# cherrymx_rgb_8row_breakout.net
KiCad netlist of a schematic drawn in EAGLE
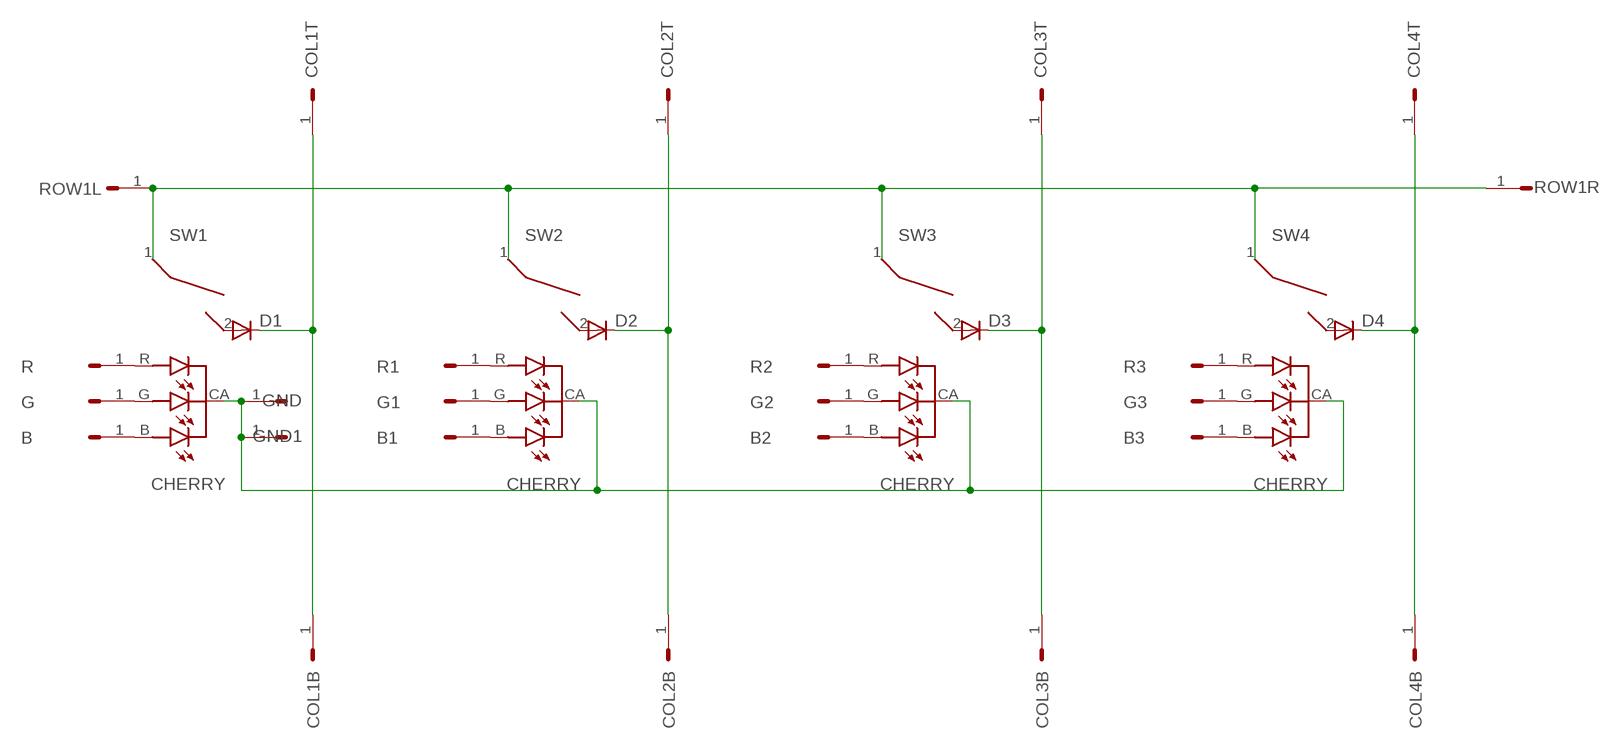
[diagram p0: schematic, sheet 1]

(export (version "E")
  (design (tool "Eeschema 10.0.6"))
  (components
    (comp (ref "B")
      (value "HEADER/MALE/01")
      (footprint "eagle-import:HEADER_MALE_01")
      (libsource (lib "eagle-import") (part "HEADER/MALE/01"))
    )
    (comp (ref "B1")
      (value "HEADER/MALE/01")
      (footprint "eagle-import:HEADER_MALE_01")
      (fields (field (name "SPICEPREFIX") "X"))
      (libsource (lib "eagle-import") (part "HEADER/MALE/01"))
    )
    (comp (ref "B2")
      (value "HEADER/MALE/01")
      (footprint "eagle-import:HEADER_MALE_01")
      (libsource (lib "eagle-import") (part "HEADER/MALE/01"))
    )
    (comp (ref "B3")
      (value "HEADER/MALE/01")
      (footprint "eagle-import:HEADER_MALE_01")
      (libsource (lib "eagle-import") (part "HEADER/MALE/01"))
    )
    (comp (ref "COL1B")
      (value "HEADER/MALE/01")
      (footprint "eagle-import:HEADER_MALE_01")
      (libsource (lib "eagle-import") (part "HEADER/MALE/01"))
    )
    (comp (ref "COL1T")
      (value "HEADER/MALE/01")
      (footprint "eagle-import:HEADER_MALE_01")
      (libsource (lib "eagle-import") (part "HEADER/MALE/01"))
    )
    (comp (ref "COL2B")
      (value "HEADER/MALE/01")
      (footprint "eagle-import:HEADER_MALE_01")
      (fields (field (name "SPICEPREFIX") "X"))
      (libsource (lib "eagle-import") (part "HEADER/MALE/01"))
    )
    (comp (ref "COL2T")
      (value "HEADER/MALE/01")
      (footprint "eagle-import:HEADER_MALE_01")
      (fields (field (name "SPICEPREFIX") "X"))
      (libsource (lib "eagle-import") (part "HEADER/MALE/01"))
    )
    (comp (ref "COL3B")
      (value "HEADER/MALE/01")
      (footprint "eagle-import:HEADER_MALE_01")
      (libsource (lib "eagle-import") (part "HEADER/MALE/01"))
    )
    (comp (ref "COL3T")
      (value "HEADER/MALE/01")
      (footprint "eagle-import:HEADER_MALE_01")
      (libsource (lib "eagle-import") (part "HEADER/MALE/01"))
    )
    (comp (ref "COL4B")
      (value "HEADER/MALE/01")
      (footprint "eagle-import:HEADER_MALE_01")
      (libsource (lib "eagle-import") (part "HEADER/MALE/01"))
    )
    (comp (ref "COL4T")
      (value "HEADER/MALE/01")
      (footprint "eagle-import:HEADER_MALE_01")
      (libsource (lib "eagle-import") (part "HEADER/MALE/01"))
    )
    (comp (ref "D1")
      (value "1N4148DO35-7")
      (footprint "eagle-import:DO35-7")
      (libsource (lib "eagle-import") (part "1N4148DO35-7"))
    )
    (comp (ref "D2")
      (value "1N4148DO35-7")
      (footprint "eagle-import:DO35-7")
      (fields (field (name "SPICEPREFIX") "D"))
      (libsource (lib "eagle-import") (part "1N4148DO35-7"))
    )
    (comp (ref "D3")
      (value "1N4148DO35-7")
      (footprint "eagle-import:DO35-7")
      (libsource (lib "eagle-import") (part "1N4148DO35-7"))
    )
    (comp (ref "D4")
      (value "1N4148DO35-7")
      (footprint "eagle-import:DO35-7")
      (libsource (lib "eagle-import") (part "1N4148DO35-7"))
    )
    (comp (ref "G")
      (value "HEADER/MALE/01")
      (footprint "eagle-import:HEADER_MALE_01")
      (libsource (lib "eagle-import") (part "HEADER/MALE/01"))
    )
    (comp (ref "G1")
      (value "HEADER/MALE/01")
      (footprint "eagle-import:HEADER_MALE_01")
      (fields (field (name "SPICEPREFIX") "X"))
      (libsource (lib "eagle-import") (part "HEADER/MALE/01"))
    )
    (comp (ref "G2")
      (value "HEADER/MALE/01")
      (footprint "eagle-import:HEADER_MALE_01")
      (libsource (lib "eagle-import") (part "HEADER/MALE/01"))
    )
    (comp (ref "G3")
      (value "HEADER/MALE/01")
      (footprint "eagle-import:HEADER_MALE_01")
      (libsource (lib "eagle-import") (part "HEADER/MALE/01"))
    )
    (comp (ref "GND")
      (value "HEADER/MALE/01")
      (footprint "eagle-import:HEADER_MALE_01")
      (libsource (lib "eagle-import") (part "HEADER/MALE/01"))
    )
    (comp (ref "GND1")
      (value "HEADER/MALE/01")
      (footprint "eagle-import:HEADER_MALE_01")
      (libsource (lib "eagle-import") (part "HEADER/MALE/01"))
    )
    (comp (ref "R")
      (value "HEADER/MALE/01")
      (footprint "eagle-import:HEADER_MALE_01")
      (libsource (lib "eagle-import") (part "HEADER/MALE/01"))
    )
    (comp (ref "R1")
      (value "HEADER/MALE/01")
      (footprint "eagle-import:HEADER_MALE_01")
      (fields (field (name "SPICEPREFIX") "X"))
      (libsource (lib "eagle-import") (part "HEADER/MALE/01"))
    )
    (comp (ref "R2")
      (value "HEADER/MALE/01")
      (footprint "eagle-import:HEADER_MALE_01")
      (libsource (lib "eagle-import") (part "HEADER/MALE/01"))
    )
    (comp (ref "R3")
      (value "HEADER/MALE/01")
      (footprint "eagle-import:HEADER_MALE_01")
      (libsource (lib "eagle-import") (part "HEADER/MALE/01"))
    )
    (comp (ref "ROW1L")
      (value "HEADER/MALE/01")
      (footprint "eagle-import:HEADER_MALE_01")
      (libsource (lib "eagle-import") (part "HEADER/MALE/01"))
    )
    (comp (ref "ROW1R")
      (value "HEADER/MALE/01")
      (footprint "eagle-import:HEADER_MALE_01")
      (libsource (lib "eagle-import") (part "HEADER/MALE/01"))
    )
    (comp (ref "SW1")
      (value "CHERRY")
      (footprint "eagle-import:SWITCH_CHERRY_MX_RGB")
      (libsource (lib "eagle-import") (part "SWITCH_CHERRY_MX_RGBSWITCH_CHERRY_MX_RGB"))
    )
    (comp (ref "SW2")
      (value "CHERRY")
      (footprint "eagle-import:SWITCH_CHERRY_MX_RGB")
      (fields (field (name "SPICEPREFIX") "X"))
      (libsource (lib "eagle-import") (part "SWITCH_CHERRY_MX_RGBSWITCH_CHERRY_MX_RGB"))
    )
    (comp (ref "SW3")
      (value "CHERRY")
      (footprint "eagle-import:SWITCH_CHERRY_MX_RGB")
      (libsource (lib "eagle-import") (part "SWITCH_CHERRY_MX_RGBSWITCH_CHERRY_MX_RGB"))
    )
    (comp (ref "SW4")
      (value "CHERRY")
      (footprint "eagle-import:SWITCH_CHERRY_MX_RGB")
      (libsource (lib "eagle-import") (part "SWITCH_CHERRY_MX_RGBSWITCH_CHERRY_MX_RGB"))
    )
  )
  (nets
    (net (code "1") (name "Net-(B-3)") (class "Default")
      (node (ref "B") (pin "1") (pinfunction "3_1") (pintype "passive"))
      (node (ref "SW1") (pin "B") (pinfunction "B-CAT_B") (pintype "passive"))
    )
    (net (code "2") (name "Net-(B1-3)") (class "Default")
      (node (ref "B1") (pin "1") (pinfunction "3_1") (pintype "passive"))
      (node (ref "SW2") (pin "B") (pinfunction "B-CAT_B") (pintype "passive"))
    )
    (net (code "3") (name "Net-(B2-3)") (class "Default")
      (node (ref "B2") (pin "1") (pinfunction "3_1") (pintype "passive"))
      (node (ref "SW3") (pin "B") (pinfunction "B-CAT_B") (pintype "passive"))
    )
    (net (code "4") (name "Net-(B3-3)") (class "Default")
      (node (ref "B3") (pin "1") (pinfunction "3_1") (pintype "passive"))
      (node (ref "SW4") (pin "B") (pinfunction "B-CAT_B") (pintype "passive"))
    )
    (net (code "5") (name "Net-(COL1B-3)") (class "Default")
      (node (ref "COL1B") (pin "1") (pinfunction "3_1") (pintype "passive"))
      (node (ref "COL1T") (pin "1") (pinfunction "3_1") (pintype "passive"))
      (node (ref "D1") (pin "C") (pinfunction "C_C") (pintype "passive"))
    )
    (net (code "6") (name "Net-(COL2B-3)") (class "Default")
      (node (ref "COL2B") (pin "1") (pinfunction "3_1") (pintype "passive"))
      (node (ref "COL2T") (pin "1") (pinfunction "3_1") (pintype "passive"))
      (node (ref "D2") (pin "C") (pinfunction "C_C") (pintype "passive"))
    )
    (net (code "7") (name "Net-(COL3B-3)") (class "Default")
      (node (ref "COL3B") (pin "1") (pinfunction "3_1") (pintype "passive"))
      (node (ref "COL3T") (pin "1") (pinfunction "3_1") (pintype "passive"))
      (node (ref "D3") (pin "C") (pinfunction "C_C") (pintype "passive"))
    )
    (net (code "8") (name "Net-(COL4B-3)") (class "Default")
      (node (ref "COL4B") (pin "1") (pinfunction "3_1") (pintype "passive"))
      (node (ref "COL4T") (pin "1") (pinfunction "3_1") (pintype "passive"))
      (node (ref "D4") (pin "C") (pinfunction "C_C") (pintype "passive"))
    )
    (net (code "9") (name "Net-(D1-PadA)") (class "Default")
      (node (ref "D1") (pin "A") (pinfunction "A_A") (pintype "passive"))
      (node (ref "SW1") (pin "2") (pinfunction "2_2") (pintype "passive"))
    )
    (net (code "10") (name "Net-(D2-PadA)") (class "Default")
      (node (ref "D2") (pin "A") (pinfunction "A_A") (pintype "passive"))
      (node (ref "SW2") (pin "2") (pinfunction "2_2") (pintype "passive"))
    )
    (net (code "11") (name "Net-(D3-PadA)") (class "Default")
      (node (ref "D3") (pin "A") (pinfunction "A_A") (pintype "passive"))
      (node (ref "SW3") (pin "2") (pinfunction "2_2") (pintype "passive"))
    )
    (net (code "12") (name "Net-(D4-PadA)") (class "Default")
      (node (ref "D4") (pin "A") (pinfunction "A_A") (pintype "passive"))
      (node (ref "SW4") (pin "2") (pinfunction "2_2") (pintype "passive"))
    )
    (net (code "13") (name "Net-(G-3)") (class "Default")
      (node (ref "G") (pin "1") (pinfunction "3_1") (pintype "passive"))
      (node (ref "SW1") (pin "G") (pinfunction "G-CAT_G") (pintype "passive"))
    )
    (net (code "14") (name "Net-(G1-3)") (class "Default")
      (node (ref "G1") (pin "1") (pinfunction "3_1") (pintype "passive"))
      (node (ref "SW2") (pin "G") (pinfunction "G-CAT_G") (pintype "passive"))
    )
    (net (code "15") (name "Net-(G2-3)") (class "Default")
      (node (ref "G2") (pin "1") (pinfunction "3_1") (pintype "passive"))
      (node (ref "SW3") (pin "G") (pinfunction "G-CAT_G") (pintype "passive"))
    )
    (net (code "16") (name "Net-(G3-3)") (class "Default")
      (node (ref "G3") (pin "1") (pinfunction "3_1") (pintype "passive"))
      (node (ref "SW4") (pin "G") (pinfunction "G-CAT_G") (pintype "passive"))
    )
    (net (code "17") (name "Net-(GND-3)") (class "Default")
      (node (ref "GND") (pin "1") (pinfunction "3_1") (pintype "passive"))
      (node (ref "GND1") (pin "1") (pinfunction "3_1") (pintype "passive"))
      (node (ref "SW1") (pin "CA") (pinfunction "COMMON-ANODE_CA") (pintype "passive"))
      (node (ref "SW2") (pin "CA") (pinfunction "COMMON-ANODE_CA") (pintype "passive"))
      (node (ref "SW3") (pin "CA") (pinfunction "COMMON-ANODE_CA") (pintype "passive"))
      (node (ref "SW4") (pin "CA") (pinfunction "COMMON-ANODE_CA") (pintype "passive"))
    )
    (net (code "18") (name "Net-(R-3)") (class "Default")
      (node (ref "R") (pin "1") (pinfunction "3_1") (pintype "passive"))
      (node (ref "SW1") (pin "R") (pinfunction "R-CAT_R") (pintype "passive"))
    )
    (net (code "19") (name "Net-(R1-3)") (class "Default")
      (node (ref "R1") (pin "1") (pinfunction "3_1") (pintype "passive"))
      (node (ref "SW2") (pin "R") (pinfunction "R-CAT_R") (pintype "passive"))
    )
    (net (code "20") (name "Net-(R2-3)") (class "Default")
      (node (ref "R2") (pin "1") (pinfunction "3_1") (pintype "passive"))
      (node (ref "SW3") (pin "R") (pinfunction "R-CAT_R") (pintype "passive"))
    )
    (net (code "21") (name "Net-(R3-3)") (class "Default")
      (node (ref "R3") (pin "1") (pinfunction "3_1") (pintype "passive"))
      (node (ref "SW4") (pin "R") (pinfunction "R-CAT_R") (pintype "passive"))
    )
    (net (code "22") (name "Net-(ROW1L-3)") (class "Default")
      (node (ref "ROW1L") (pin "1") (pinfunction "3_1") (pintype "passive"))
      (node (ref "ROW1R") (pin "1") (pinfunction "3_1") (pintype "passive"))
      (node (ref "SW1") (pin "1") (pinfunction "1_1") (pintype "passive"))
      (node (ref "SW2") (pin "1") (pinfunction "1_1") (pintype "passive"))
      (node (ref "SW3") (pin "1") (pinfunction "1_1") (pintype "passive"))
      (node (ref "SW4") (pin "1") (pinfunction "1_1") (pintype "passive"))
    )
  )
)
